# badge_arvore_natal.net
KiCad netlist of a schematic drawn in EAGLE
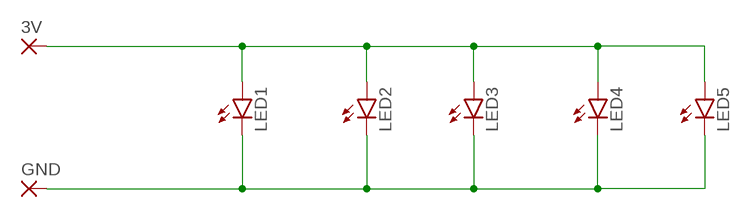
[diagram p0: schematic, sheet 1]

(export (version "E")
  (design (tool "Eeschema 10.0.6"))
  (components
    (comp (ref "3V")
      (value "SMD2")
      (footprint "eagle-import:SMD1,27-2,54")
      (libsource (lib "eagle-import") (part "SMD2"))
    )
    (comp (ref "GND")
      (value "SMD2")
      (footprint "eagle-import:SMD1,27-2,54")
      (libsource (lib "eagle-import") (part "SMD2"))
    )
    (comp (ref "LED1")
      (value "LEDCHIPLED_0805")
      (footprint "eagle-import:CHIPLED_0805")
      (libsource (lib "eagle-import") (part "LEDCHIPLED_0805"))
    )
    (comp (ref "LED2")
      (value "LEDCHIPLED_0805")
      (footprint "eagle-import:CHIPLED_0805")
      (libsource (lib "eagle-import") (part "LEDCHIPLED_0805"))
    )
    (comp (ref "LED3")
      (value "LEDCHIPLED_0805")
      (footprint "eagle-import:CHIPLED_0805")
      (libsource (lib "eagle-import") (part "LEDCHIPLED_0805"))
    )
    (comp (ref "LED4")
      (value "LEDCHIPLED_0805")
      (footprint "eagle-import:CHIPLED_0805")
      (libsource (lib "eagle-import") (part "LEDCHIPLED_0805"))
    )
    (comp (ref "LED5")
      (value "LEDCHIPLED_0805")
      (footprint "eagle-import:CHIPLED_0805")
      (libsource (lib "eagle-import") (part "LEDCHIPLED_0805"))
    )
  )
  (nets
    (net (code "1") (name "Net-(3V-P)") (class "Default")
      (node (ref "3V") (pin "1") (pinfunction "P_1") (pintype "passive"))
      (node (ref "LED1") (pin "A") (pinfunction "A_A") (pintype "passive"))
      (node (ref "LED2") (pin "A") (pinfunction "A_A") (pintype "passive"))
      (node (ref "LED3") (pin "A") (pinfunction "A_A") (pintype "passive"))
      (node (ref "LED4") (pin "A") (pinfunction "A_A") (pintype "passive"))
      (node (ref "LED5") (pin "A") (pinfunction "A_A") (pintype "passive"))
    )
    (net (code "2") (name "Net-(GND-P)") (class "Default")
      (node (ref "GND") (pin "1") (pinfunction "P_1") (pintype "passive"))
      (node (ref "LED1") (pin "C") (pinfunction "C_C") (pintype "passive"))
      (node (ref "LED2") (pin "C") (pinfunction "C_C") (pintype "passive"))
      (node (ref "LED3") (pin "C") (pinfunction "C_C") (pintype "passive"))
      (node (ref "LED4") (pin "C") (pinfunction "C_C") (pintype "passive"))
      (node (ref "LED5") (pin "C") (pinfunction "C_C") (pintype "passive"))
    )
  )
)
